# Misc.net
KiCad netlist of a schematic drawn in Altium Designer
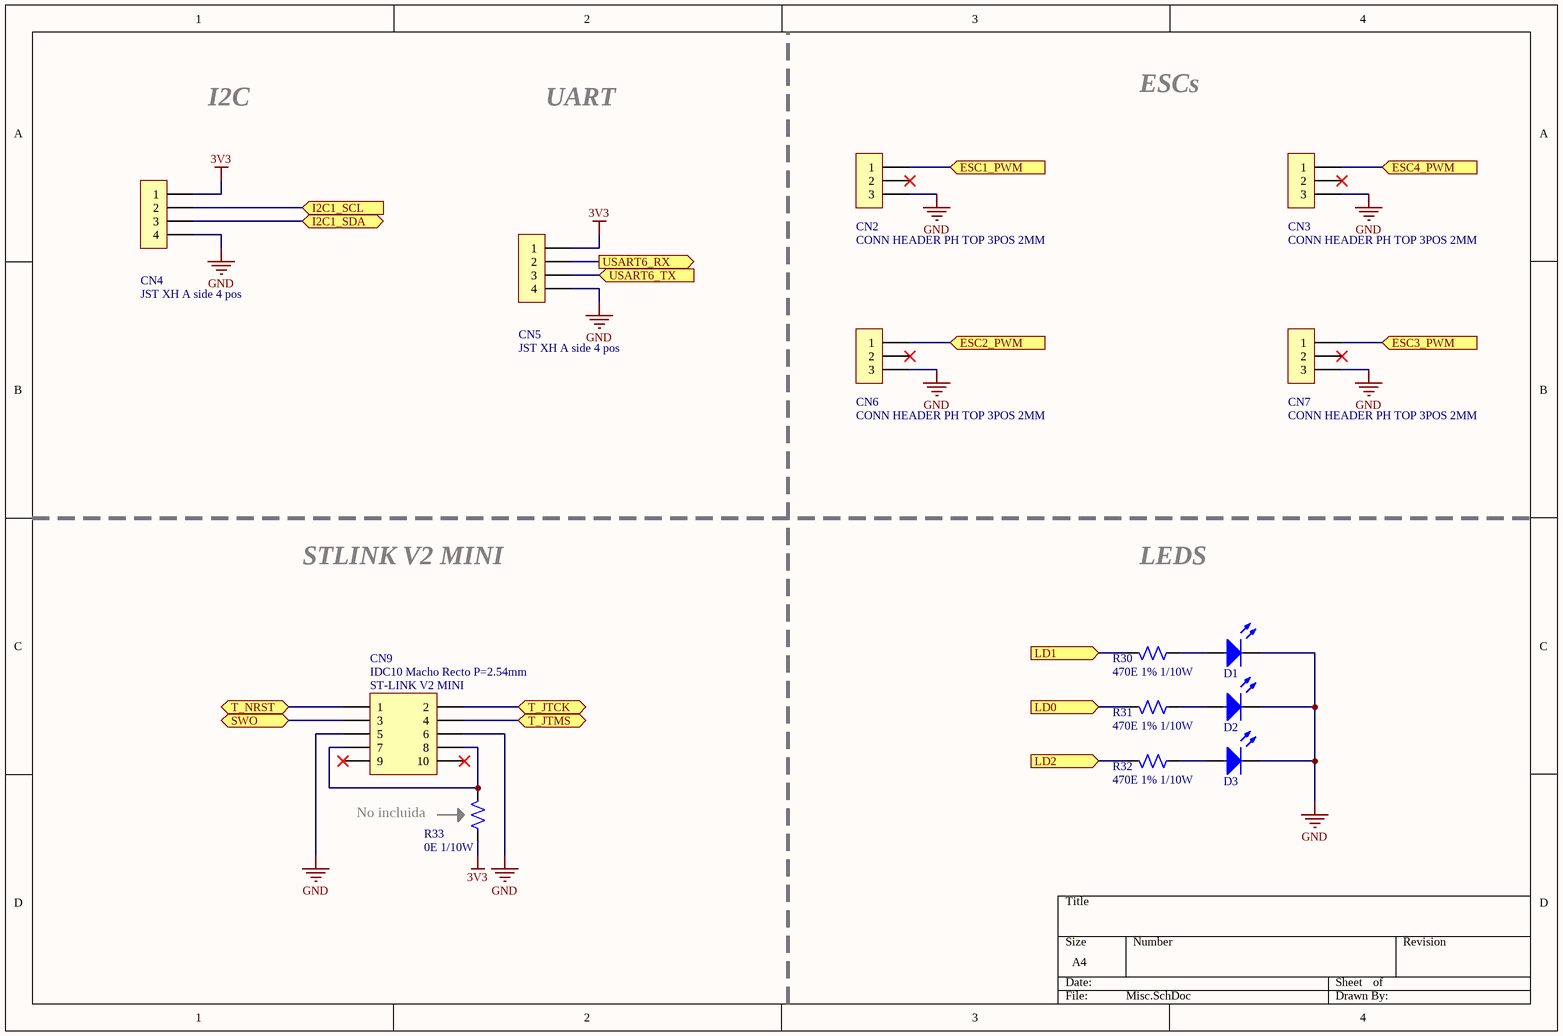
[diagram p0: Misc.SchDoc]

(export (version "E")
  (design (tool "Eeschema 10.0.6"))
  (components
    (comp (ref "CN2")
      (value "CONN HEADER PH TOP 3POS 2MM")
      (footprint "JST-PH_3")
      (description "Header, 3-pin")
      (libsource (lib "HW_Dron_V2") (part "Header_3"))
    )
    (comp (ref "CN3")
      (value "CONN HEADER PH TOP 3POS 2MM")
      (footprint "JST-PH_3")
      (description "Header, 3-pin")
      (libsource (lib "HW_Dron_V2") (part "Header_3"))
    )
    (comp (ref "CN4")
      (value "JST XH A side 4 pos")
      (footprint "S4B-XH-A")
      (description "Header, 4-pin")
      (libsource (lib "HW_Dron_V2") (part "Header_4"))
    )
    (comp (ref "CN5")
      (value "JST XH A side 4 pos")
      (footprint "S4B-XH-A")
      (description "Header, 4-pin")
      (libsource (lib "HW_Dron_V2") (part "Header_4"))
    )
    (comp (ref "CN6")
      (value "CONN HEADER PH TOP 3POS 2MM")
      (footprint "JST-PH_3")
      (description "Header, 3-pin")
      (libsource (lib "HW_Dron_V2") (part "Header_3"))
    )
    (comp (ref "CN7")
      (value "CONN HEADER PH TOP 3POS 2MM")
      (footprint "JST-PH_3")
      (description "Header, 3-pin")
      (libsource (lib "HW_Dron_V2") (part "Header_3"))
    )
    (comp (ref "CN9")
      (value "IDC10 Macho Recto P=2.54mm")
      (footprint "IDC10M")
      (description "Header, 5x2-pin pinout horizontal")
      (fields (field (name "ALTIUM_UNNAMED_1") "ST-LINK V2 MINI"))
      (libsource (lib "HW_Dron_V2") (part "Header_5x2H"))
    )
    (comp (ref "D1")
      (value "Led")
      (footprint "LED_0805")
      (description "Diodo Led")
      (libsource (lib "HW_Dron_V2") (part "Led"))
    )
    (comp (ref "D2")
      (value "Led")
      (footprint "LED_0805")
      (description "Diodo Led")
      (libsource (lib "HW_Dron_V2") (part "Led"))
    )
    (comp (ref "D3")
      (value "Led")
      (footprint "LED_0805")
      (description "Diodo Led")
      (libsource (lib "HW_Dron_V2") (part "Led"))
    )
    (comp (ref "R30")
      (value "470E 1% 1/10W")
      (footprint "R0603")
      (description "Resistencia")
      (libsource (lib "HW_Dron_V2") (part "Resistor"))
    )
    (comp (ref "R31")
      (value "470E 1% 1/10W")
      (footprint "R0603")
      (description "Resistencia")
      (libsource (lib "HW_Dron_V2") (part "Resistor"))
    )
    (comp (ref "R32")
      (value "470E 1% 1/10W")
      (footprint "R0603")
      (description "Resistencia")
      (libsource (lib "HW_Dron_V2") (part "Resistor"))
    )
    (comp (ref "R33")
      (value "0E 1/10W")
      (footprint "R0805")
      (description "Resistencia")
      (libsource (lib "HW_Dron_V2") (part "Resistor"))
    )
  )
  (nets
    (net (code "1") (name "/ESC1_PWM") (class "Default")
      (node (ref "CN2") (pin "1") (pinfunction "1_1") (pintype "passive"))
    )
    (net (code "2") (name "/ESC2_PWM") (class "Default")
      (node (ref "CN6") (pin "1") (pinfunction "1_1") (pintype "passive"))
    )
    (net (code "3") (name "/ESC3_PWM") (class "Default")
      (node (ref "CN7") (pin "1") (pinfunction "1_1") (pintype "passive"))
    )
    (net (code "4") (name "/ESC4_PWM") (class "Default")
      (node (ref "CN3") (pin "1") (pinfunction "1_1") (pintype "passive"))
    )
    (net (code "5") (name "/I2C1_SCL") (class "Default")
      (node (ref "CN4") (pin "2") (pinfunction "2_2") (pintype "passive"))
    )
    (net (code "6") (name "/I2C1_SDA") (class "Default")
      (node (ref "CN4") (pin "3") (pinfunction "3_3") (pintype "passive"))
    )
    (net (code "7") (name "/LD0") (class "Default")
      (node (ref "R31") (pin "2") (pinfunction "2_2") (pintype "passive"))
    )
    (net (code "8") (name "/LD1") (class "Default")
      (node (ref "R30") (pin "2") (pinfunction "2_2") (pintype "passive"))
    )
    (net (code "9") (name "/LD2") (class "Default")
      (node (ref "R32") (pin "2") (pinfunction "2_2") (pintype "passive"))
    )
    (net (code "10") (name "/SWO") (class "Default")
      (node (ref "CN9") (pin "3") (pinfunction "3_3") (pintype "passive"))
    )
    (net (code "11") (name "/T_JTCK") (class "Default")
      (node (ref "CN9") (pin "2") (pinfunction "2_2") (pintype "passive"))
    )
    (net (code "12") (name "/T_JTMS") (class "Default")
      (node (ref "CN9") (pin "4") (pinfunction "4_4") (pintype "passive"))
    )
    (net (code "13") (name "/T_NRST") (class "Default")
      (node (ref "CN9") (pin "1") (pinfunction "1_1") (pintype "passive"))
    )
    (net (code "14") (name "/USART6_RX") (class "Default")
      (node (ref "CN5") (pin "2") (pinfunction "2_2") (pintype "passive"))
    )
    (net (code "15") (name "/USART6_TX") (class "Default")
      (node (ref "CN5") (pin "3") (pinfunction "3_3") (pintype "passive"))
    )
    (net (code "16") (name "3V3") (class "Default")
      (node (ref "CN4") (pin "1") (pinfunction "1_1") (pintype "passive"))
      (node (ref "CN5") (pin "1") (pinfunction "1_1") (pintype "passive"))
      (node (ref "R33") (pin "1") (pinfunction "1_1") (pintype "passive"))
    )
    (net (code "17") (name "GND") (class "Default")
      (node (ref "CN2") (pin "3") (pinfunction "3_3") (pintype "passive"))
      (node (ref "CN3") (pin "3") (pinfunction "3_3") (pintype "passive"))
      (node (ref "CN4") (pin "4") (pinfunction "4_4") (pintype "passive"))
      (node (ref "CN5") (pin "4") (pinfunction "4_4") (pintype "passive"))
      (node (ref "CN6") (pin "3") (pinfunction "3_3") (pintype "passive"))
      (node (ref "CN7") (pin "3") (pinfunction "3_3") (pintype "passive"))
      (node (ref "CN9") (pin "5") (pinfunction "5_5") (pintype "passive"))
      (node (ref "CN9") (pin "6") (pinfunction "6_6") (pintype "passive"))
      (node (ref "D1") (pin "2") (pinfunction "2_2") (pintype "passive"))
      (node (ref "D2") (pin "2") (pinfunction "2_2") (pintype "passive"))
      (node (ref "D3") (pin "2") (pinfunction "2_2") (pintype "passive"))
    )
    (net (code "18") (name "Net-(CN9-Pad7)") (class "Default")
      (node (ref "CN9") (pin "7") (pinfunction "7_7") (pintype "passive"))
      (node (ref "CN9") (pin "8") (pinfunction "8_8") (pintype "passive"))
      (node (ref "R33") (pin "2") (pinfunction "2_2") (pintype "passive"))
    )
    (net (code "19") (name "Net-(D1-Pad1)") (class "Default")
      (node (ref "D1") (pin "1") (pinfunction "1_1") (pintype "passive"))
      (node (ref "R30") (pin "1") (pinfunction "1_1") (pintype "passive"))
    )
    (net (code "20") (name "Net-(D2-Pad1)") (class "Default")
      (node (ref "D2") (pin "1") (pinfunction "1_1") (pintype "passive"))
      (node (ref "R31") (pin "1") (pinfunction "1_1") (pintype "passive"))
    )
    (net (code "21") (name "Net-(D3-Pad1)") (class "Default")
      (node (ref "D3") (pin "1") (pinfunction "1_1") (pintype "passive"))
      (node (ref "R32") (pin "1") (pinfunction "1_1") (pintype "passive"))
    )
    (net (code "22") (name "unconnected-(CN2-Pad2)") (class "Default")
      (node (ref "CN2") (pin "2") (pinfunction "2_2") (pintype "passive+no_connect"))
    )
    (net (code "23") (name "unconnected-(CN3-Pad2)") (class "Default")
      (node (ref "CN3") (pin "2") (pinfunction "2_2") (pintype "passive+no_connect"))
    )
    (net (code "24") (name "unconnected-(CN6-Pad2)") (class "Default")
      (node (ref "CN6") (pin "2") (pinfunction "2_2") (pintype "passive+no_connect"))
    )
    (net (code "25") (name "unconnected-(CN7-Pad2)") (class "Default")
      (node (ref "CN7") (pin "2") (pinfunction "2_2") (pintype "passive+no_connect"))
    )
    (net (code "26") (name "unconnected-(CN9-Pad9)") (class "Default")
      (node (ref "CN9") (pin "9") (pinfunction "9_9") (pintype "passive+no_connect"))
    )
    (net (code "27") (name "unconnected-(CN9-Pad10)") (class "Default")
      (node (ref "CN9") (pin "10") (pinfunction "10_10") (pintype "passive+no_connect"))
    )
  )
)
